# strobe_3.net
KiCad netlist of a schematic drawn in EAGLE
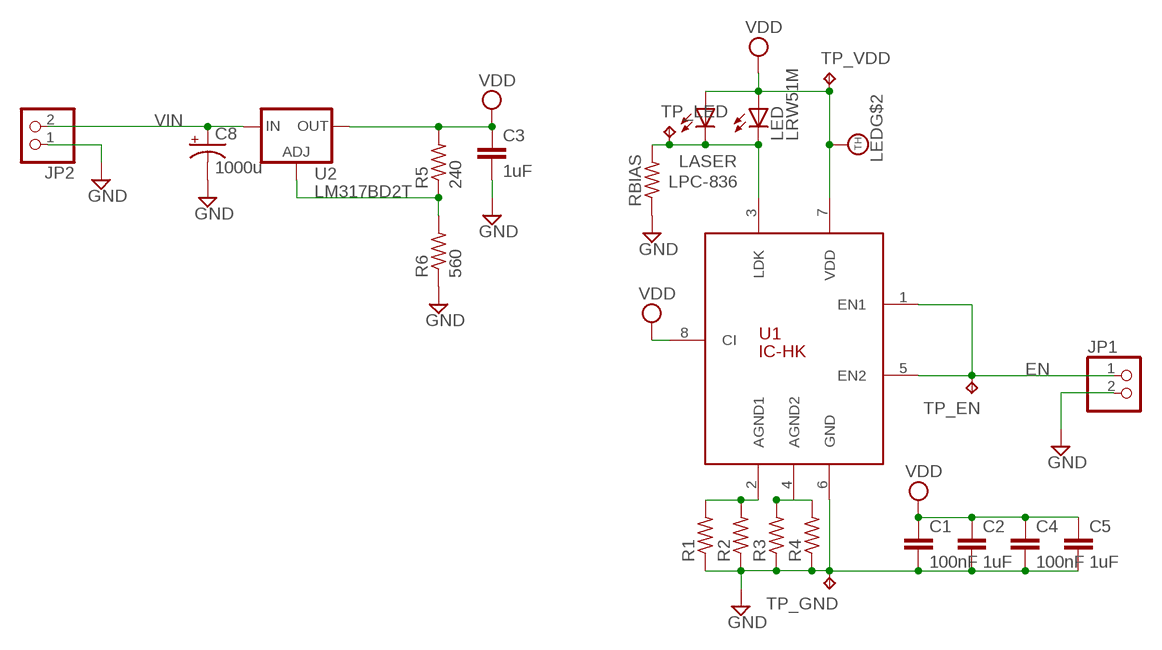
[diagram p0: schematic, sheet 1]

(export (version "E")
  (design (tool "Eeschema 10.0.6"))
  (components
    (comp (ref "C1")
      (value "100nF")
      (footprint "eagle-import:C0805")
      (libsource (lib "eagle-import") (part "C-EUC0805"))
    )
    (comp (ref "C2")
      (value "1uF")
      (footprint "eagle-import:C0805")
      (libsource (lib "eagle-import") (part "C-EUC0805"))
    )
    (comp (ref "C3")
      (value "1uF")
      (footprint "eagle-import:C0805")
      (libsource (lib "eagle-import") (part "C-EUC0805"))
    )
    (comp (ref "C4")
      (value "100nF")
      (footprint "eagle-import:C0805")
      (libsource (lib "eagle-import") (part "C-EUC0805"))
    )
    (comp (ref "C5")
      (value "1uF")
      (footprint "eagle-import:C0805")
      (libsource (lib "eagle-import") (part "C-EUC0805"))
    )
    (comp (ref "C8")
      (value "1000u")
      (footprint "eagle-import:E5-10,5")
      (libsource (lib "eagle-import") (part "CPOL-USE5-10.5"))
    )
    (comp (ref "JP1")
      (value "PINHD-1X2")
      (footprint "eagle-import:1X02")
      (libsource (lib "eagle-import") (part "PINHD-1X2"))
    )
    (comp (ref "JP2")
      (value "PINHD-1X2")
      (footprint "eagle-import:1X02")
      (libsource (lib "eagle-import") (part "PINHD-1X2"))
    )
    (comp (ref "LASER")
      (value "LPC-836")
      (footprint "eagle-import:LASER-TO18")
      (libsource (lib "eagle-import") (part "LPC-836"))
    )
    (comp (ref "LED")
      (value "LRW51M")
      (footprint "eagle-import:W51")
      (libsource (lib "eagle-import") (part "W51MLR"))
    )
    (comp (ref "R1")
      (value "R-US_R1206")
      (footprint "eagle-import:R1206")
      (libsource (lib "eagle-import") (part "R-US_R1206"))
    )
    (comp (ref "R2")
      (value "R-US_R1206")
      (footprint "eagle-import:R1206")
      (libsource (lib "eagle-import") (part "R-US_R1206"))
    )
    (comp (ref "R3")
      (value "R-US_R1206")
      (footprint "eagle-import:R1206")
      (libsource (lib "eagle-import") (part "R-US_R1206"))
    )
    (comp (ref "R4")
      (value "R-US_R1206")
      (footprint "eagle-import:R1206")
      (libsource (lib "eagle-import") (part "R-US_R1206"))
    )
    (comp (ref "R5")
      (value "240")
      (footprint "eagle-import:R1206")
      (libsource (lib "eagle-import") (part "R-US_R1206"))
    )
    (comp (ref "R6")
      (value "560")
      (footprint "eagle-import:R1206")
      (libsource (lib "eagle-import") (part "R-US_R1206"))
    )
    (comp (ref "RBIAS")
      (value "R-US_R1206")
      (footprint "eagle-import:R1206")
      (libsource (lib "eagle-import") (part "R-US_R1206"))
    )
    (comp (ref "TP_EN")
      (value "TPPAD1-17")
      (footprint "eagle-import:P1-17")
      (libsource (lib "eagle-import") (part "TPPAD1-17"))
    )
    (comp (ref "TP_GND")
      (value "TPPAD1-17")
      (footprint "eagle-import:P1-17")
      (libsource (lib "eagle-import") (part "TPPAD1-17"))
    )
    (comp (ref "TP_LED")
      (value "TPPAD1-17")
      (footprint "eagle-import:P1-17")
      (libsource (lib "eagle-import") (part "TPPAD1-17"))
    )
    (comp (ref "TP_VDD")
      (value "TPPAD1-17")
      (footprint "eagle-import:P1-17")
      (libsource (lib "eagle-import") (part "TPPAD1-17"))
    )
    (comp (ref "U1")
      (value "IC-HK")
      (footprint "eagle-import:SO8")
      (libsource (lib "eagle-import") (part "IC-HK"))
    )
    (comp (ref "U2")
      (value "LM317BD2T")
      (footprint "eagle-import:D2PACK")
      (libsource (lib "eagle-import") (part "LM317?BD2T"))
    )
  )
  (nets
    (net (code "1") (name "/EN") (class "Default")
      (node (ref "JP1") (pin "1") (pinfunction "1_1") (pintype "passive"))
      (node (ref "TP_EN") (pin "TP") (pinfunction "TP_TP") (pintype "input"))
      (node (ref "U1") (pin "1") (pinfunction "EN1_1") (pintype "bidirectional"))
      (node (ref "U1") (pin "5") (pinfunction "EN2_5") (pintype "bidirectional"))
    )
    (net (code "2") (name "/VIN") (class "Default")
      (node (ref "C8") (pin "+") (pinfunction "+_+") (pintype "passive"))
      (node (ref "JP2") (pin "2") (pinfunction "2_2") (pintype "passive"))
      (node (ref "U2") (pin "3") (pinfunction "IN_3") (pintype "input"))
    )
    (net (code "3") (name "GND") (class "Default")
      (node (ref "C1") (pin "2") (pinfunction "2_2") (pintype "passive"))
      (node (ref "C2") (pin "2") (pinfunction "2_2") (pintype "passive"))
      (node (ref "C3") (pin "2") (pinfunction "2_2") (pintype "passive"))
      (node (ref "C4") (pin "2") (pinfunction "2_2") (pintype "passive"))
      (node (ref "C5") (pin "2") (pinfunction "2_2") (pintype "passive"))
      (node (ref "C8") (pin "-") (pinfunction "-_-") (pintype "passive"))
      (node (ref "JP1") (pin "2") (pinfunction "2_2") (pintype "passive"))
      (node (ref "JP2") (pin "1") (pinfunction "1_1") (pintype "passive"))
      (node (ref "R1") (pin "1") (pinfunction "1_1") (pintype "passive"))
      (node (ref "R2") (pin "1") (pinfunction "1_1") (pintype "passive"))
      (node (ref "R3") (pin "1") (pinfunction "1_1") (pintype "passive"))
      (node (ref "R4") (pin "1") (pinfunction "1_1") (pintype "passive"))
      (node (ref "R6") (pin "1") (pinfunction "1_1") (pintype "passive"))
      (node (ref "RBIAS") (pin "1") (pinfunction "1_1") (pintype "passive"))
      (node (ref "TP_GND") (pin "TP") (pinfunction "TP_TP") (pintype "input"))
      (node (ref "U1") (pin "6") (pinfunction "GND_6") (pintype "power_in"))
    )
    (net (code "4") (name "Net-(LASER-C)") (class "Default")
      (node (ref "LASER") (pin "3") (pinfunction "C_3") (pintype "passive"))
      (node (ref "LED") (pin "C") (pinfunction "C_C") (pintype "passive"))
      (node (ref "RBIAS") (pin "2") (pinfunction "2_2") (pintype "passive"))
      (node (ref "TP_LED") (pin "TP") (pinfunction "TP_TP") (pintype "input"))
      (node (ref "U1") (pin "3") (pinfunction "LDK_3") (pintype "passive"))
    )
    (net (code "5") (name "Net-(U1-AGND1)") (class "Default")
      (node (ref "R1") (pin "2") (pinfunction "2_2") (pintype "passive"))
      (node (ref "R2") (pin "2") (pinfunction "2_2") (pintype "passive"))
      (node (ref "U1") (pin "2") (pinfunction "AGND1_2") (pintype "passive"))
    )
    (net (code "6") (name "Net-(U1-AGND2)") (class "Default")
      (node (ref "R3") (pin "2") (pinfunction "2_2") (pintype "passive"))
      (node (ref "R4") (pin "2") (pinfunction "2_2") (pintype "passive"))
      (node (ref "U1") (pin "4") (pinfunction "AGND2_4") (pintype "passive"))
    )
    (net (code "7") (name "Net-(U2-ADJ)") (class "Default")
      (node (ref "R5") (pin "1") (pinfunction "1_1") (pintype "passive"))
      (node (ref "R6") (pin "2") (pinfunction "2_2") (pintype "passive"))
      (node (ref "U2") (pin "1") (pinfunction "ADJ_1") (pintype "input"))
    )
    (net (code "8") (name "VDD") (class "Default")
      (node (ref "C1") (pin "1") (pinfunction "1_1") (pintype "passive"))
      (node (ref "C2") (pin "1") (pinfunction "1_1") (pintype "passive"))
      (node (ref "C3") (pin "1") (pinfunction "1_1") (pintype "passive"))
      (node (ref "C4") (pin "1") (pinfunction "1_1") (pintype "passive"))
      (node (ref "C5") (pin "1") (pinfunction "1_1") (pintype "passive"))
      (node (ref "LASER") (pin "1") (pinfunction "A_1") (pintype "passive"))
      (node (ref "LED") (pin "A") (pinfunction "A_A") (pintype "passive"))
      (node (ref "LED") (pin "TH@1") (pinfunction "TH_TH@1") (pintype "passive"))
      (node (ref "LED") (pin "TH@2") (pinfunction "TH_TH@2") (pintype "passive"))
      (node (ref "LED") (pin "TH@3") (pinfunction "TH_TH@3") (pintype "passive"))
      (node (ref "R5") (pin "2") (pinfunction "2_2") (pintype "passive"))
      (node (ref "TP_VDD") (pin "TP") (pinfunction "TP_TP") (pintype "input"))
      (node (ref "U1") (pin "7") (pinfunction "VDD_7") (pintype "power_in"))
      (node (ref "U1") (pin "8") (pinfunction "CI_8") (pintype "passive"))
      (node (ref "U2") (pin "2") (pinfunction "OUT_2") (pintype "passive"))
    )
  )
)
